# BLE_--_HM-10_--_Carduino_Breakout_v1_0_2.net
KiCad netlist of a schematic drawn in EAGLE
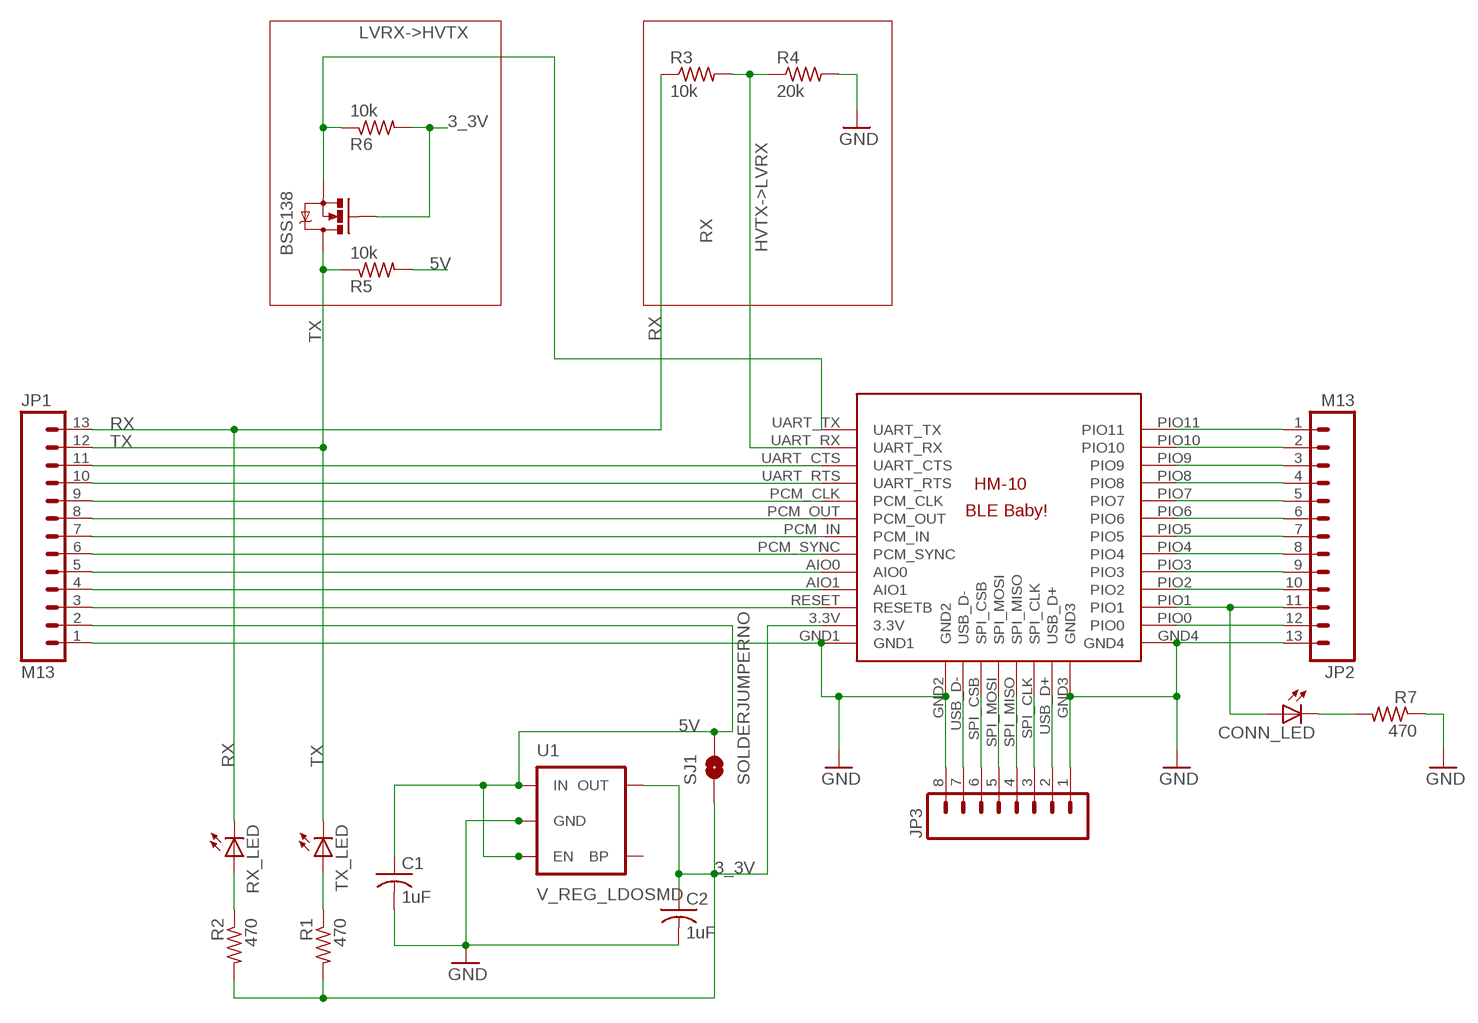
[diagram p0: schematic, sheet 1]

(export (version "E")
  (design (tool "Eeschema 10.0.6"))
  (components
    (comp (ref "BSS138")
      (value "MOSFET-NCHANNELSMD")
      (footprint "eagle-import:SOT23-3")
      (libsource (lib "eagle-import") (part "MOSFET-NCHANNELSMD"))
    )
    (comp (ref "C1")
      (value "1uF")
      (footprint "eagle-import:C0805K")
      (libsource (lib "eagle-import") (part "C-USC0805K"))
    )
    (comp (ref "C2")
      (value "1uF")
      (footprint "eagle-import:C0805K")
      (libsource (lib "eagle-import") (part "C-USC0805K"))
    )
    (comp (ref "CONN_LED")
      (value "LED0603")
      (footprint "eagle-import:LED-0603")
      (libsource (lib "eagle-import") (part "LED0603"))
    )
    (comp (ref "JP1")
      (value "M13")
      (footprint "eagle-import:1X13")
      (libsource (lib "eagle-import") (part "M13"))
    )
    (comp (ref "JP2")
      (value "M13")
      (footprint "eagle-import:1X13")
      (libsource (lib "eagle-import") (part "M13"))
    )
    (comp (ref "JP3")
      (value "M081X08")
      (footprint "eagle-import:1X08")
      (libsource (lib "eagle-import") (part "M081X08"))
    )
    (comp (ref "R1")
      (value "470")
      (footprint "eagle-import:M0805")
      (libsource (lib "eagle-import") (part "R-US_M0805"))
    )
    (comp (ref "R2")
      (value "470")
      (footprint "eagle-import:M0805")
      (libsource (lib "eagle-import") (part "R-US_M0805"))
    )
    (comp (ref "R3")
      (value "10k")
      (footprint "eagle-import:M0805")
      (libsource (lib "eagle-import") (part "R-US_M0805"))
    )
    (comp (ref "R4")
      (value "20k")
      (footprint "eagle-import:M0805")
      (libsource (lib "eagle-import") (part "R-US_M0805"))
    )
    (comp (ref "R5")
      (value "10k")
      (footprint "eagle-import:M0805")
      (libsource (lib "eagle-import") (part "R-US_M0805"))
    )
    (comp (ref "R6")
      (value "10k")
      (footprint "eagle-import:M0805")
      (libsource (lib "eagle-import") (part "R-US_M0805"))
    )
    (comp (ref "R7")
      (value "470")
      (footprint "eagle-import:M0805")
      (libsource (lib "eagle-import") (part "R-US_M0805"))
    )
    (comp (ref "RX_LED")
      (value "LED0603")
      (footprint "eagle-import:LED-0603")
      (libsource (lib "eagle-import") (part "LED0603"))
    )
    (comp (ref "SJ1")
      (value "SOLDERJUMPERNO")
      (footprint "eagle-import:SJ_2S-NO")
      (libsource (lib "eagle-import") (part "SOLDERJUMPERNO"))
    )
    (comp (ref "TX_LED")
      (value "LED0603")
      (footprint "eagle-import:LED-0603")
      (libsource (lib "eagle-import") (part "LED0603"))
    )
    (comp (ref "U$1")
      (value "BLE-HM-10")
      (footprint "eagle-import:BLE-HM-10")
      (libsource (lib "eagle-import") (part "BLE-HM-10"))
    )
    (comp (ref "U1")
      (value "V_REG_LDOSMD")
      (footprint "eagle-import:SOT23-5")
      (libsource (lib "eagle-import") (part "V_REG_LDOSMD"))
    )
  )
  (nets
    (net (code "1") (name "/3_3V") (class "Default")
      (node (ref "BSS138") (pin "1") (pinfunction "G_1") (pintype "passive"))
      (node (ref "C2") (pin "1") (pinfunction "1_1") (pintype "passive"))
      (node (ref "R1") (pin "2") (pinfunction "2_2") (pintype "passive"))
      (node (ref "R2") (pin "2") (pinfunction "2_2") (pintype "passive"))
      (node (ref "R6") (pin "2") (pinfunction "2_2") (pintype "passive"))
      (node (ref "SJ1") (pin "1") (pinfunction "1_1") (pintype "passive"))
      (node (ref "U$1") (pin "3.3V") (pinfunction "3.3V_3.3V") (pintype "bidirectional"))
      (node (ref "U1") (pin "5") (pinfunction "OUT_5") (pintype "passive"))
    )
    (net (code "2") (name "/5V") (class "Default")
      (node (ref "C1") (pin "1") (pinfunction "1_1") (pintype "passive"))
      (node (ref "JP1") (pin "2") (pinfunction "2_2") (pintype "passive"))
      (node (ref "R5") (pin "2") (pinfunction "2_2") (pintype "passive"))
      (node (ref "SJ1") (pin "2") (pinfunction "2_2") (pintype "passive"))
      (node (ref "U1") (pin "1") (pinfunction "IN_1") (pintype "input"))
      (node (ref "U1") (pin "3") (pinfunction "EN_3") (pintype "input"))
    )
    (net (code "3") (name "/HVTX->LVRX") (class "Default")
      (node (ref "R3") (pin "2") (pinfunction "2_2") (pintype "passive"))
      (node (ref "R4") (pin "1") (pinfunction "1_1") (pintype "passive"))
      (node (ref "U$1") (pin "UART_RX") (pinfunction "UART_RX_UART_RX") (pintype "bidirectional"))
    )
    (net (code "4") (name "/LVRX->HVTX") (class "Default")
      (node (ref "BSS138") (pin "2") (pinfunction "S_2") (pintype "passive"))
      (node (ref "R6") (pin "1") (pinfunction "1_1") (pintype "passive"))
      (node (ref "U$1") (pin "UART_TX") (pinfunction "UART_TX_UART_TX") (pintype "bidirectional"))
    )
    (net (code "5") (name "/RX") (class "Default")
      (node (ref "JP1") (pin "13") (pinfunction "13_13") (pintype "passive"))
      (node (ref "R3") (pin "1") (pinfunction "1_1") (pintype "passive"))
      (node (ref "RX_LED") (pin "C") (pinfunction "C_C") (pintype "passive"))
    )
    (net (code "6") (name "/TX") (class "Default")
      (node (ref "BSS138") (pin "3") (pinfunction "D_3") (pintype "passive"))
      (node (ref "JP1") (pin "12") (pinfunction "12_12") (pintype "passive"))
      (node (ref "R5") (pin "1") (pinfunction "1_1") (pintype "passive"))
      (node (ref "TX_LED") (pin "C") (pinfunction "C_C") (pintype "passive"))
    )
    (net (code "7") (name "GND") (class "Default")
      (node (ref "C1") (pin "2") (pinfunction "2_2") (pintype "passive"))
      (node (ref "C2") (pin "2") (pinfunction "2_2") (pintype "passive"))
      (node (ref "JP1") (pin "1") (pinfunction "1_1") (pintype "passive"))
      (node (ref "JP2") (pin "13") (pinfunction "13_13") (pintype "passive"))
      (node (ref "JP3") (pin "1") (pinfunction "1_1") (pintype "passive"))
      (node (ref "JP3") (pin "8") (pinfunction "8_8") (pintype "passive"))
      (node (ref "R4") (pin "2") (pinfunction "2_2") (pintype "passive"))
      (node (ref "R7") (pin "1") (pinfunction "1_1") (pintype "passive"))
      (node (ref "U$1") (pin "GND1") (pinfunction "GND1_GND1") (pintype "bidirectional"))
      (node (ref "U$1") (pin "GND2") (pinfunction "GND2_GND2") (pintype "bidirectional"))
      (node (ref "U$1") (pin "GND3") (pinfunction "GND3_GND3") (pintype "bidirectional"))
      (node (ref "U$1") (pin "GND4") (pinfunction "GND4_GND4") (pintype "bidirectional"))
      (node (ref "U1") (pin "2") (pinfunction "GND_2") (pintype "input"))
    )
    (net (code "8") (name "Net-(CONN_LED-PadA)") (class "Default")
      (node (ref "CONN_LED") (pin "A") (pinfunction "A_A") (pintype "passive"))
      (node (ref "JP2") (pin "11") (pinfunction "11_11") (pintype "passive"))
      (node (ref "U$1") (pin "PIO1") (pinfunction "PIO1_PIO1") (pintype "bidirectional"))
    )
    (net (code "9") (name "Net-(CONN_LED-PadC)") (class "Default")
      (node (ref "CONN_LED") (pin "C") (pinfunction "C_C") (pintype "passive"))
      (node (ref "R7") (pin "2") (pinfunction "2_2") (pintype "passive"))
    )
    (net (code "10") (name "Net-(JP1-Pad4)") (class "Default")
      (node (ref "JP1") (pin "4") (pinfunction "4_4") (pintype "passive"))
      (node (ref "U$1") (pin "AIO1") (pinfunction "AIO1_AIO1") (pintype "bidirectional"))
    )
    (net (code "11") (name "Net-(JP1-Pad5)") (class "Default")
      (node (ref "JP1") (pin "5") (pinfunction "5_5") (pintype "passive"))
      (node (ref "U$1") (pin "AIO0") (pinfunction "AIO0_AIO0") (pintype "bidirectional"))
    )
    (net (code "12") (name "Net-(JP1-Pad6)") (class "Default")
      (node (ref "JP1") (pin "6") (pinfunction "6_6") (pintype "passive"))
      (node (ref "U$1") (pin "PCM_SYNC") (pinfunction "PCM_SYNC_PCM_SYNC") (pintype "bidirectional"))
    )
    (net (code "13") (name "Net-(JP1-Pad7)") (class "Default")
      (node (ref "JP1") (pin "7") (pinfunction "7_7") (pintype "passive"))
      (node (ref "U$1") (pin "PCM_IN") (pinfunction "PCM_IN_PCM_IN") (pintype "bidirectional"))
    )
    (net (code "14") (name "Net-(JP1-Pad8)") (class "Default")
      (node (ref "JP1") (pin "8") (pinfunction "8_8") (pintype "passive"))
      (node (ref "U$1") (pin "PCM_OUT") (pinfunction "PCM_OUT_PCM_OUT") (pintype "bidirectional"))
    )
    (net (code "15") (name "Net-(JP1-Pad9)") (class "Default")
      (node (ref "JP1") (pin "9") (pinfunction "9_9") (pintype "passive"))
      (node (ref "U$1") (pin "PCM_CLK") (pinfunction "PCM_CLK_PCM_CLK") (pintype "bidirectional"))
    )
    (net (code "16") (name "Net-(JP1-Pad10)") (class "Default")
      (node (ref "JP1") (pin "10") (pinfunction "10_10") (pintype "passive"))
      (node (ref "U$1") (pin "UART_RTS") (pinfunction "UART_RTS_UART_RTS") (pintype "bidirectional"))
    )
    (net (code "17") (name "Net-(JP1-Pad11)") (class "Default")
      (node (ref "JP1") (pin "11") (pinfunction "11_11") (pintype "passive"))
      (node (ref "U$1") (pin "UART_CTS") (pinfunction "UART_CTS_UART_CTS") (pintype "bidirectional"))
    )
    (net (code "18") (name "Net-(JP2-Pad1)") (class "Default")
      (node (ref "JP2") (pin "1") (pinfunction "1_1") (pintype "passive"))
      (node (ref "U$1") (pin "PIO11") (pinfunction "PIO11_PIO11") (pintype "bidirectional"))
    )
    (net (code "19") (name "Net-(JP2-Pad2)") (class "Default")
      (node (ref "JP2") (pin "2") (pinfunction "2_2") (pintype "passive"))
      (node (ref "U$1") (pin "PIO10") (pinfunction "PIO10_PIO10") (pintype "bidirectional"))
    )
    (net (code "20") (name "Net-(JP2-Pad3)") (class "Default")
      (node (ref "JP2") (pin "3") (pinfunction "3_3") (pintype "passive"))
      (node (ref "U$1") (pin "PIO9") (pinfunction "PIO9_PIO9") (pintype "bidirectional"))
    )
    (net (code "21") (name "Net-(JP2-Pad4)") (class "Default")
      (node (ref "JP2") (pin "4") (pinfunction "4_4") (pintype "passive"))
      (node (ref "U$1") (pin "PIO8") (pinfunction "PIO8_PIO8") (pintype "bidirectional"))
    )
    (net (code "22") (name "Net-(JP2-Pad5)") (class "Default")
      (node (ref "JP2") (pin "5") (pinfunction "5_5") (pintype "passive"))
      (node (ref "U$1") (pin "PIO7") (pinfunction "PIO7_PIO7") (pintype "bidirectional"))
    )
    (net (code "23") (name "Net-(JP2-Pad6)") (class "Default")
      (node (ref "JP2") (pin "6") (pinfunction "6_6") (pintype "passive"))
      (node (ref "U$1") (pin "PIO6") (pinfunction "PIO6_PIO6") (pintype "bidirectional"))
    )
    (net (code "24") (name "Net-(JP2-Pad7)") (class "Default")
      (node (ref "JP2") (pin "7") (pinfunction "7_7") (pintype "passive"))
      (node (ref "U$1") (pin "PIO5") (pinfunction "PIO5_PIO5") (pintype "bidirectional"))
    )
    (net (code "25") (name "Net-(JP2-Pad8)") (class "Default")
      (node (ref "JP2") (pin "8") (pinfunction "8_8") (pintype "passive"))
      (node (ref "U$1") (pin "PIO4") (pinfunction "PIO4_PIO4") (pintype "bidirectional"))
    )
    (net (code "26") (name "Net-(JP2-Pad9)") (class "Default")
      (node (ref "JP2") (pin "9") (pinfunction "9_9") (pintype "passive"))
      (node (ref "U$1") (pin "PIO3") (pinfunction "PIO3_PIO3") (pintype "bidirectional"))
    )
    (net (code "27") (name "Net-(JP2-Pad10)") (class "Default")
      (node (ref "JP2") (pin "10") (pinfunction "10_10") (pintype "passive"))
      (node (ref "U$1") (pin "PIO2") (pinfunction "PIO2_PIO2") (pintype "bidirectional"))
    )
    (net (code "28") (name "Net-(JP2-Pad12)") (class "Default")
      (node (ref "JP2") (pin "12") (pinfunction "12_12") (pintype "passive"))
      (node (ref "U$1") (pin "PIO0") (pinfunction "PIO0_PIO0") (pintype "bidirectional"))
    )
    (net (code "29") (name "Net-(JP3-Pad2)") (class "Default")
      (node (ref "JP3") (pin "2") (pinfunction "2_2") (pintype "passive"))
      (node (ref "U$1") (pin "USB_D+") (pinfunction "USB_D+_USB_D+") (pintype "bidirectional"))
    )
    (net (code "30") (name "Net-(JP3-Pad3)") (class "Default")
      (node (ref "JP3") (pin "3") (pinfunction "3_3") (pintype "passive"))
      (node (ref "U$1") (pin "SPI_CLK") (pinfunction "SPI_CLK_SPI_CLK") (pintype "bidirectional"))
    )
    (net (code "31") (name "Net-(JP3-Pad4)") (class "Default")
      (node (ref "JP3") (pin "4") (pinfunction "4_4") (pintype "passive"))
      (node (ref "U$1") (pin "SPI_MISO") (pinfunction "SPI_MISO_SPI_MISO") (pintype "bidirectional"))
    )
    (net (code "32") (name "Net-(JP3-Pad5)") (class "Default")
      (node (ref "JP3") (pin "5") (pinfunction "5_5") (pintype "passive"))
      (node (ref "U$1") (pin "SPI_MOSI") (pinfunction "SPI_MOSI_SPI_MOSI") (pintype "bidirectional"))
    )
    (net (code "33") (name "Net-(JP3-Pad6)") (class "Default")
      (node (ref "JP3") (pin "6") (pinfunction "6_6") (pintype "passive"))
      (node (ref "U$1") (pin "SPI_CSB") (pinfunction "SPI_CSB_SPI_CSB") (pintype "bidirectional"))
    )
    (net (code "34") (name "Net-(JP3-Pad7)") (class "Default")
      (node (ref "JP3") (pin "7") (pinfunction "7_7") (pintype "passive"))
      (node (ref "U$1") (pin "USB_D-") (pinfunction "USB_D-_USB_D-") (pintype "bidirectional"))
    )
    (net (code "35") (name "Net-(R1-Pad1)") (class "Default")
      (node (ref "R1") (pin "1") (pinfunction "1_1") (pintype "passive"))
      (node (ref "TX_LED") (pin "A") (pinfunction "A_A") (pintype "passive"))
    )
    (net (code "36") (name "Net-(R2-Pad1)") (class "Default")
      (node (ref "R2") (pin "1") (pinfunction "1_1") (pintype "passive"))
      (node (ref "RX_LED") (pin "A") (pinfunction "A_A") (pintype "passive"))
    )
    (net (code "37") (name "Net-(U$1-RESETB)") (class "Default")
      (node (ref "JP1") (pin "3") (pinfunction "3_3") (pintype "passive"))
      (node (ref "U$1") (pin "RESET") (pinfunction "RESETB_RESET") (pintype "bidirectional"))
    )
    (net (code "38") (name "unconnected-(U1-BP-Pad4)") (class "Default")
      (node (ref "U1") (pin "4") (pinfunction "BP_4") (pintype "input"))
    )
  )
)
